# Power_Distribution_-_Pi.net
KiCad netlist of a schematic drawn in Altium Designer
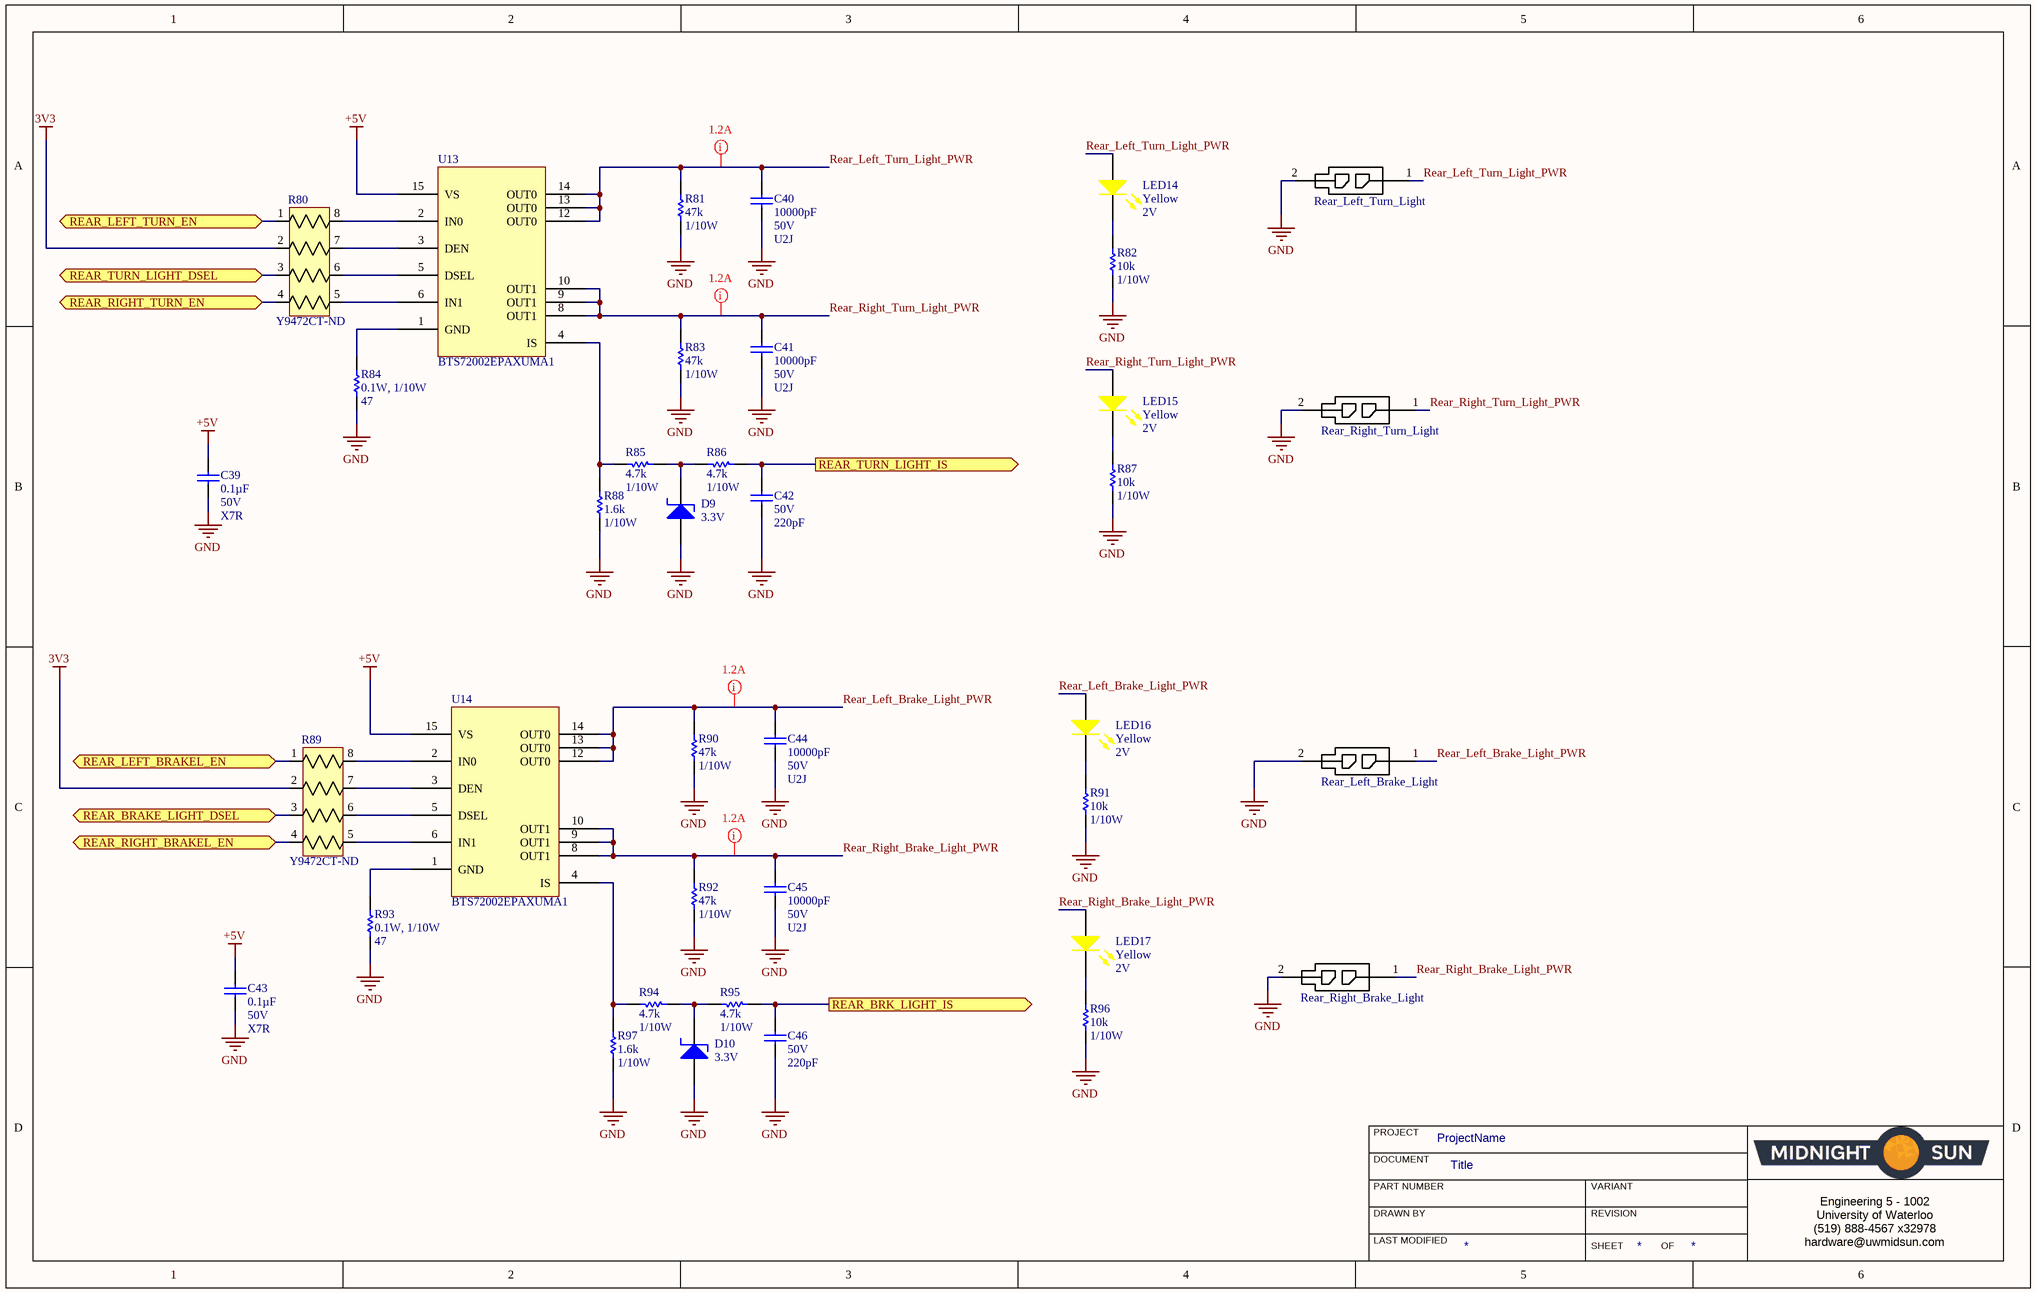
[diagram p0: Power Distribution - Pi.SchDoc]

(export (version "E")
  (design (tool "Eeschema 10.0.6"))
  (components
    (comp (ref "C39")
      (value "CAP CER 0.1UF 50V 10% X7R 0603")
      (footprint "CAP, 0603")
      (description "0.10µF ±10% 50V Ceramic Capacitor X7R 0603 (1608 Metric)")
      (fields
        (field (name "TOLERANCE") "±10%")
        (field (name "CAPACITANCE") "0.1µF")
        (field (name "VOLTAGE") "50V")
        (field (name "TEMPERATURE COEFFICIENT") "X7R")
      )
      (libsource (lib "Schematic Diagrams") (part "CAP CER 0.1UF 50V 10% X7R 0603"))
    )
    (comp (ref "C40")
      (value "CAP CER 10nF 50V 5% X7R 0603")
      (footprint "CAP, 0603")
      (description "10000pF ±5% 50V Ceramic Capacitor U2J 0603 (1608 Metric)")
      (fields
        (field (name "TOLERANCE") "±5%")
        (field (name "CAPACITANCE") "10000pF")
        (field (name "VOLTAGE") "50V")
        (field (name "TEMPERATURE COEFFICIENT") "U2J")
      )
      (libsource (lib "Schematic Diagrams") (part "CAP CER 10nF 50V 5% X7R 0603"))
    )
    (comp (ref "C41")
      (value "CAP CER 10nF 50V 5% X7R 0603")
      (footprint "CAP, 0603")
      (description "10000pF ±5% 50V Ceramic Capacitor U2J 0603 (1608 Metric)")
      (fields
        (field (name "TOLERANCE") "±5%")
        (field (name "CAPACITANCE") "10000pF")
        (field (name "VOLTAGE") "50V")
        (field (name "TEMPERATURE COEFFICIENT") "U2J")
      )
      (libsource (lib "Schematic Diagrams") (part "CAP CER 10nF 50V 5% X7R 0603"))
    )
    (comp (ref "C42")
      (value "CAP CER 220PF 50V C0G/NP0 0603")
      (footprint "CAP, 0603")
      (description "220pF ±5% 50V Ceramic Capacitor C0G, NP0 0603 (1608 Metric)")
      (fields
        (field (name "MANUFACTURER") "KEMET")
        (field (name "TOLERANCE") "5%")
        (field (name "VOLTAGE RATING") "50V")
        (field (name "CAPACITANCE") "220pF")
      )
      (libsource (lib "Schematic Diagrams") (part "CAP CER 220PF 50V C0G/NP0 0603"))
    )
    (comp (ref "C43")
      (value "CAP CER 0.1UF 50V 10% X7R 0603")
      (footprint "CAP, 0603")
      (description "0.10µF ±10% 50V Ceramic Capacitor X7R 0603 (1608 Metric)")
      (fields
        (field (name "TOLERANCE") "±10%")
        (field (name "CAPACITANCE") "0.1µF")
        (field (name "VOLTAGE") "50V")
        (field (name "TEMPERATURE COEFFICIENT") "X7R")
      )
      (libsource (lib "Schematic Diagrams") (part "CAP CER 0.1UF 50V 10% X7R 0603"))
    )
    (comp (ref "C44")
      (value "CAP CER 10nF 50V 5% X7R 0603")
      (footprint "CAP, 0603")
      (description "10000pF ±5% 50V Ceramic Capacitor U2J 0603 (1608 Metric)")
      (fields
        (field (name "TOLERANCE") "±5%")
        (field (name "CAPACITANCE") "10000pF")
        (field (name "VOLTAGE") "50V")
        (field (name "TEMPERATURE COEFFICIENT") "U2J")
      )
      (libsource (lib "Schematic Diagrams") (part "CAP CER 10nF 50V 5% X7R 0603"))
    )
    (comp (ref "C45")
      (value "CAP CER 10nF 50V 5% X7R 0603")
      (footprint "CAP, 0603")
      (description "10000pF ±5% 50V Ceramic Capacitor U2J 0603 (1608 Metric)")
      (fields
        (field (name "TOLERANCE") "±5%")
        (field (name "CAPACITANCE") "10000pF")
        (field (name "VOLTAGE") "50V")
        (field (name "TEMPERATURE COEFFICIENT") "U2J")
      )
      (libsource (lib "Schematic Diagrams") (part "CAP CER 10nF 50V 5% X7R 0603"))
    )
    (comp (ref "C46")
      (value "CAP CER 220PF 50V C0G/NP0 0603")
      (footprint "CAP, 0603")
      (description "220pF ±5% 50V Ceramic Capacitor C0G, NP0 0603 (1608 Metric)")
      (fields
        (field (name "MANUFACTURER") "KEMET")
        (field (name "TOLERANCE") "5%")
        (field (name "VOLTAGE RATING") "50V")
        (field (name "CAPACITANCE") "220pF")
      )
      (libsource (lib "Schematic Diagrams") (part "CAP CER 220PF 50V C0G/NP0 0603"))
    )
    (comp (ref "D9")
      (value "DIODE ZENER 3.3V 200MW SOD323")
      (footprint "sod-323")
      (description "Zener Diode 3.3V 200mW ±5% Surface Mount SOD-323")
      (fields (field (name "VOLTAGE") "3.3V"))
      (libsource (lib "Schematic Diagrams") (part "DIODE ZENER 3.3V 200MW SOD323"))
    )
    (comp (ref "D10")
      (value "DIODE ZENER 3.3V 200MW SOD323")
      (footprint "sod-323")
      (description "Zener Diode 3.3V 200mW ±5% Surface Mount SOD-323")
      (fields (field (name "VOLTAGE") "3.3V"))
      (libsource (lib "Schematic Diagrams") (part "DIODE ZENER 3.3V 200MW SOD323"))
    )
    (comp (ref "LED14")
      (value "LED YELLOW CLEAR 2.1V 0603")
      (footprint "LED_0603")
      (description "Yellow 590nm LED Indication - Discrete 2V 0603 (1608 Metric)")
      (fields
        (field (name "MANUFACTURER") "Wurth Electronics Inc.")
        (field (name "MANUFACTURER PART NUMBER") "150060YS75000")
        (field (name "COLOR") "Yellow")
        (field (name "VOLTAGE - FORWARD (VF) (TYP)") "2V")
      )
      (libsource (lib "Schematic Diagrams") (part "LED YELLOW CLEAR 2.1V 0603"))
    )
    (comp (ref "LED15")
      (value "LED YELLOW CLEAR 2.1V 0603")
      (footprint "LED_0603")
      (description "Yellow 590nm LED Indication - Discrete 2V 0603 (1608 Metric)")
      (fields
        (field (name "MANUFACTURER") "Wurth Electronics Inc.")
        (field (name "MANUFACTURER PART NUMBER") "150060YS75000")
        (field (name "COLOR") "Yellow")
        (field (name "VOLTAGE - FORWARD (VF) (TYP)") "2V")
      )
      (libsource (lib "Schematic Diagrams") (part "LED YELLOW CLEAR 2.1V 0603"))
    )
    (comp (ref "LED16")
      (value "LED YELLOW CLEAR 2.1V 0603")
      (footprint "LED_0603")
      (description "Yellow 590nm LED Indication - Discrete 2V 0603 (1608 Metric)")
      (fields
        (field (name "MANUFACTURER") "Wurth Electronics Inc.")
        (field (name "MANUFACTURER PART NUMBER") "150060YS75000")
        (field (name "COLOR") "Yellow")
        (field (name "VOLTAGE - FORWARD (VF) (TYP)") "2V")
      )
      (libsource (lib "Schematic Diagrams") (part "LED YELLOW CLEAR 2.1V 0603"))
    )
    (comp (ref "LED17")
      (value "LED YELLOW CLEAR 2.1V 0603")
      (footprint "LED_0603")
      (description "Yellow 590nm LED Indication - Discrete 2V 0603 (1608 Metric)")
      (fields
        (field (name "MANUFACTURER") "Wurth Electronics Inc.")
        (field (name "MANUFACTURER PART NUMBER") "150060YS75000")
        (field (name "COLOR") "Yellow")
        (field (name "VOLTAGE - FORWARD (VF) (TYP)") "2V")
      )
      (libsource (lib "Schematic Diagrams") (part "LED YELLOW CLEAR 2.1V 0603"))
    )
    (comp (ref "R80")
      (value "RES ARRAY 4 RES 4.7K OHM 1206")
      (footprint "RES ARRAY 4RES 1206")
      (fields (field (name "TOLERANCE") "±5%") (field (name "SUPPLIER PART NUMBER 1") "Y9472CT-ND"))
      (libsource (lib "Schematic Diagrams") (part "RES ARRAY 4 RES 4.7K OHM 1206"))
    )
    (comp (ref "R81")
      (value "RES 47K OHM 1% 1/10W 0603")
      (footprint "RES, 0603")
      (description "47 kOhms ±1% 0.1W, 1/10W Chip Resistor 0603 (1608 Metric) Automotive AEC-Q200 Thick Film")
      (fields
        (field (name "MANUFACTURER") "Panasonic")
        (field (name "MANUFACTURER PART NUMBER") "ERJ3EKF4702V")
        (field (name "RESISTANCE") "47k")
        (field (name "POWER RATING") "1/10W")
      )
      (libsource (lib "Schematic Diagrams") (part "RES 47K OHM 1% 1/10W 0603"))
    )
    (comp (ref "R82")
      (value "RES 10K OHM 1% 1/10W 0603")
      (footprint "RES, 0603")
      (description "RES SMD 10K OHM 1% 1/10W 0603")
      (fields
        (field (name "TOLERANCE") "±1%")
        (field (name "RESISTANCE") "10k")
        (field (name "POWER") "1/10W")
      )
      (libsource (lib "Schematic Diagrams") (part "RES 10K OHM 1% 1/10W 0603"))
    )
    (comp (ref "R83")
      (value "RES 47K OHM 1% 1/10W 0603")
      (footprint "RES, 0603")
      (description "47 kOhms ±1% 0.1W, 1/10W Chip Resistor 0603 (1608 Metric) Automotive AEC-Q200 Thick Film")
      (fields
        (field (name "MANUFACTURER") "Panasonic")
        (field (name "MANUFACTURER PART NUMBER") "ERJ3EKF4702V")
        (field (name "RESISTANCE") "47k")
        (field (name "POWER RATING") "1/10W")
      )
      (libsource (lib "Schematic Diagrams") (part "RES 47K OHM 1% 1/10W 0603"))
    )
    (comp (ref "R84")
      (value "RES SMD 47 OHM 1% 1/10W 0603")
      (footprint "RES, 0603")
      (fields
        (field (name "TOLERANCE") "±1%")
        (field (name "POWER (WATTS)") "0.1W, 1/10W")
        (field (name "VALUES") "47")
      )
      (libsource (lib "Schematic Diagrams") (part "RES SMD 47 OHM 1% 1/10W 0603"))
    )
    (comp (ref "R85")
      (value "RES 4.7K OHM 1% 1/10W 0603")
      (footprint "RES, 0603")
      (description "4.7k Ohm ±1% 0.1W, 1/10W Chip Resistor 0603 (1608 Metric) Moisture Resistant Thick Film")
      (fields
        (field (name "TOLERANCE") "±1%")
        (field (name "RESISTANCE (OHMS)") "4.7k")
        (field (name "POWER (WATTS)") "1/10W")
      )
      (libsource (lib "Schematic Diagrams") (part "RES 4.7K OHM 1% 1/10W 0603"))
    )
    (comp (ref "R86")
      (value "RES 4.7K OHM 1% 1/10W 0603")
      (footprint "RES, 0603")
      (description "4.7k Ohm ±1% 0.1W, 1/10W Chip Resistor 0603 (1608 Metric) Moisture Resistant Thick Film")
      (fields
        (field (name "TOLERANCE") "±1%")
        (field (name "RESISTANCE (OHMS)") "4.7k")
        (field (name "POWER (WATTS)") "1/10W")
      )
      (libsource (lib "Schematic Diagrams") (part "RES 4.7K OHM 1% 1/10W 0603"))
    )
    (comp (ref "R87")
      (value "RES 10K OHM 1% 1/10W 0603")
      (footprint "RES, 0603")
      (description "RES SMD 10K OHM 1% 1/10W 0603")
      (fields
        (field (name "TOLERANCE") "±1%")
        (field (name "RESISTANCE") "10k")
        (field (name "POWER") "1/10W")
      )
      (libsource (lib "Schematic Diagrams") (part "RES 10K OHM 1% 1/10W 0603"))
    )
    (comp (ref "R88")
      (value "RES 1.6K OHM 1% 1/10W 0603")
      (footprint "RES, 0603")
      (description "1.6 kOhms ±1% 0.1W, 1/10W Chip Resistor 0603 (1608 Metric) Moisture Resistant Thick Film")
      (fields
        (field (name "MANUFACTURER") "Yageo")
        (field (name "MANUFACTURER PART NUMBER") "RC0603FR-071K6L")
        (field (name "RESISTANCE") "1.6k")
        (field (name "POWER RATING") "1/10W")
      )
      (libsource (lib "Schematic Diagrams") (part "RES 1.6K OHM 1% 1/10W 0603"))
    )
    (comp (ref "R89")
      (value "RES ARRAY 4 RES 4.7K OHM 1206")
      (footprint "RES ARRAY 4RES 1206")
      (fields (field (name "TOLERANCE") "±5%") (field (name "SUPPLIER PART NUMBER 1") "Y9472CT-ND"))
      (libsource (lib "Schematic Diagrams") (part "RES ARRAY 4 RES 4.7K OHM 1206"))
    )
    (comp (ref "R90")
      (value "RES 47K OHM 1% 1/10W 0603")
      (footprint "RES, 0603")
      (description "47 kOhms ±1% 0.1W, 1/10W Chip Resistor 0603 (1608 Metric) Automotive AEC-Q200 Thick Film")
      (fields
        (field (name "MANUFACTURER") "Panasonic")
        (field (name "MANUFACTURER PART NUMBER") "ERJ3EKF4702V")
        (field (name "RESISTANCE") "47k")
        (field (name "POWER RATING") "1/10W")
      )
      (libsource (lib "Schematic Diagrams") (part "RES 47K OHM 1% 1/10W 0603"))
    )
    (comp (ref "R91")
      (value "RES 10K OHM 1% 1/10W 0603")
      (footprint "RES, 0603")
      (description "RES SMD 10K OHM 1% 1/10W 0603")
      (fields
        (field (name "TOLERANCE") "±1%")
        (field (name "RESISTANCE") "10k")
        (field (name "POWER") "1/10W")
      )
      (libsource (lib "Schematic Diagrams") (part "RES 10K OHM 1% 1/10W 0603"))
    )
    (comp (ref "R92")
      (value "RES 47K OHM 1% 1/10W 0603")
      (footprint "RES, 0603")
      (description "47 kOhms ±1% 0.1W, 1/10W Chip Resistor 0603 (1608 Metric) Automotive AEC-Q200 Thick Film")
      (fields
        (field (name "MANUFACTURER") "Panasonic")
        (field (name "MANUFACTURER PART NUMBER") "ERJ3EKF4702V")
        (field (name "RESISTANCE") "47k")
        (field (name "POWER RATING") "1/10W")
      )
      (libsource (lib "Schematic Diagrams") (part "RES 47K OHM 1% 1/10W 0603"))
    )
    (comp (ref "R93")
      (value "RES SMD 47 OHM 1% 1/10W 0603")
      (footprint "RES, 0603")
      (fields
        (field (name "TOLERANCE") "±1%")
        (field (name "POWER (WATTS)") "0.1W, 1/10W")
        (field (name "VALUES") "47")
      )
      (libsource (lib "Schematic Diagrams") (part "RES SMD 47 OHM 1% 1/10W 0603"))
    )
    (comp (ref "R94")
      (value "RES 4.7K OHM 1% 1/10W 0603")
      (footprint "RES, 0603")
      (description "4.7k Ohm ±1% 0.1W, 1/10W Chip Resistor 0603 (1608 Metric) Moisture Resistant Thick Film")
      (fields
        (field (name "TOLERANCE") "±1%")
        (field (name "RESISTANCE (OHMS)") "4.7k")
        (field (name "POWER (WATTS)") "1/10W")
      )
      (libsource (lib "Schematic Diagrams") (part "RES 4.7K OHM 1% 1/10W 0603"))
    )
    (comp (ref "R95")
      (value "RES 4.7K OHM 1% 1/10W 0603")
      (footprint "RES, 0603")
      (description "4.7k Ohm ±1% 0.1W, 1/10W Chip Resistor 0603 (1608 Metric) Moisture Resistant Thick Film")
      (fields
        (field (name "TOLERANCE") "±1%")
        (field (name "RESISTANCE (OHMS)") "4.7k")
        (field (name "POWER (WATTS)") "1/10W")
      )
      (libsource (lib "Schematic Diagrams") (part "RES 4.7K OHM 1% 1/10W 0603"))
    )
    (comp (ref "R96")
      (value "RES 10K OHM 1% 1/10W 0603")
      (footprint "RES, 0603")
      (description "RES SMD 10K OHM 1% 1/10W 0603")
      (fields
        (field (name "TOLERANCE") "±1%")
        (field (name "RESISTANCE") "10k")
        (field (name "POWER") "1/10W")
      )
      (libsource (lib "Schematic Diagrams") (part "RES 10K OHM 1% 1/10W 0603"))
    )
    (comp (ref "R97")
      (value "RES 1.6K OHM 1% 1/10W 0603")
      (footprint "RES, 0603")
      (description "1.6 kOhms ±1% 0.1W, 1/10W Chip Resistor 0603 (1608 Metric) Moisture Resistant Thick Film")
      (fields
        (field (name "MANUFACTURER") "Yageo")
        (field (name "MANUFACTURER PART NUMBER") "RC0603FR-071K6L")
        (field (name "RESISTANCE") "1.6k")
        (field (name "POWER RATING") "1/10W")
      )
      (libsource (lib "Schematic Diagrams") (part "RES 1.6K OHM 1% 1/10W 0603"))
    )
    (comp (ref "Rear_Left_Brake_Light")
      (value "CONN 2POS MICRO-FIT 3mm")
      (footprint "CONN, 2POS MICRO-FIT")
      (description "Connector Header Through Hole 2 position")
      (fields (field (name "MANUFACTURER") "Molex") (field (name "MANUFACTURER PART NUMBER") "43045-0227"))
      (libsource (lib "Schematic Diagrams") (part "CONN 2POS MICRO-FIT 3mm"))
    )
    (comp (ref "Rear_Left_Turn_Light")
      (value "CONN 2POS MICRO-FIT 3mm")
      (footprint "CONN, 2POS MICRO-FIT")
      (description "Connector Header Through Hole 2 position")
      (fields (field (name "MANUFACTURER") "Molex") (field (name "MANUFACTURER PART NUMBER") "43045-0227"))
      (libsource (lib "Schematic Diagrams") (part "CONN 2POS MICRO-FIT 3mm"))
    )
    (comp (ref "Rear_Right_Brake_Light")
      (value "CONN 2POS MICRO-FIT 3mm")
      (footprint "CONN, 2POS MICRO-FIT")
      (description "Connector Header Through Hole 2 position")
      (fields (field (name "MANUFACTURER") "Molex") (field (name "MANUFACTURER PART NUMBER") "43045-0227"))
      (libsource (lib "Schematic Diagrams") (part "CONN 2POS MICRO-FIT 3mm"))
    )
    (comp (ref "Rear_Right_Turn_Light")
      (value "CONN 2POS MICRO-FIT 3mm")
      (footprint "CONN, 2POS MICRO-FIT")
      (description "Connector Header Through Hole 2 position")
      (fields (field (name "MANUFACTURER") "Molex") (field (name "MANUFACTURER PART NUMBER") "43045-0227"))
      (libsource (lib "Schematic Diagrams") (part "CONN 2POS MICRO-FIT 3mm"))
    )
    (comp (ref "U13")
      (value "IC LOAD SWITCH BTS7200-2EPA PG-TSDSO-14_1")
      (footprint "IC LOAD SWITCH PG-TSDSO-14-22")
      (description "Power Switch/Driver 1:1 N-Channel 1.2A PG-TSDSO-14-22")
      (fields
        (field (name "MANUFACTURER") "Infineon")
        (field (name "MANUFACTURER PART NUMBER") "BTS72002EPAXUMA1")
      )
      (libsource (lib "Schematic Diagrams") (part "IC LOAD SWITCH BTS7200-2EPA PG-TSDSO-14_1"))
    )
    (comp (ref "U14")
      (value "IC LOAD SWITCH BTS7200-2EPA PG-TSDSO-14_1")
      (footprint "IC LOAD SWITCH PG-TSDSO-14-22")
      (description "Power Switch/Driver 1:1 N-Channel 1.2A PG-TSDSO-14-22")
      (fields
        (field (name "MANUFACTURER") "Infineon")
        (field (name "MANUFACTURER PART NUMBER") "BTS72002EPAXUMA1")
      )
      (libsource (lib "Schematic Diagrams") (part "IC LOAD SWITCH BTS7200-2EPA PG-TSDSO-14_1"))
    )
  )
  (nets
    (net (code "1") (name "+5V") (class "Default")
      (node (ref "C39") (pin "1") (pinfunction "1_1") (pintype "passive"))
      (node (ref "C43") (pin "1") (pinfunction "1_1") (pintype "passive"))
      (node (ref "U13") (pin "15") (pinfunction "VS_15") (pintype "passive"))
      (node (ref "U14") (pin "15") (pinfunction "VS_15") (pintype "passive"))
    )
    (net (code "2") (name "/REAR_BRAKE_LIGHT_DSEL") (class "Default")
      (node (ref "R89") (pin "3") (pinfunction "3_3") (pintype "passive"))
    )
    (net (code "3") (name "/REAR_BRK_LIGHT_IS") (class "Default")
      (node (ref "C46") (pin "1") (pinfunction "1_1") (pintype "passive"))
      (node (ref "R95") (pin "1") (pinfunction "1_1") (pintype "passive"))
    )
    (net (code "4") (name "/REAR_LEFT_BRAKEL_EN") (class "Default")
      (node (ref "R89") (pin "1") (pinfunction "1_1") (pintype "passive"))
    )
    (net (code "5") (name "/REAR_LEFT_TURN_EN") (class "Default")
      (node (ref "R80") (pin "1") (pinfunction "1_1") (pintype "passive"))
    )
    (net (code "6") (name "/REAR_RIGHT_BRAKEL_EN") (class "Default")
      (node (ref "R89") (pin "4") (pinfunction "4_4") (pintype "passive"))
    )
    (net (code "7") (name "/REAR_RIGHT_TURN_EN") (class "Default")
      (node (ref "R80") (pin "4") (pinfunction "4_4") (pintype "passive"))
    )
    (net (code "8") (name "/REAR_TURN_LIGHT_DSEL") (class "Default")
      (node (ref "R80") (pin "3") (pinfunction "3_3") (pintype "passive"))
    )
    (net (code "9") (name "/REAR_TURN_LIGHT_IS") (class "Default")
      (node (ref "C42") (pin "1") (pinfunction "1_1") (pintype "passive"))
      (node (ref "R86") (pin "1") (pinfunction "1_1") (pintype "passive"))
    )
    (net (code "10") (name "/Rear_Left_Brake_Light_PWR") (class "Default")
      (node (ref "C44") (pin "1") (pinfunction "1_1") (pintype "passive"))
      (node (ref "LED16") (pin "1") (pinfunction "A_1") (pintype "passive"))
      (node (ref "R90") (pin "1") (pinfunction "1_1") (pintype "passive"))
      (node (ref "Rear_Left_Brake_Light") (pin "1") (pinfunction "1_1") (pintype "passive"))
      (node (ref "U14") (pin "12") (pinfunction "OUT0_12") (pintype "passive"))
      (node (ref "U14") (pin "13") (pinfunction "OUT0_13") (pintype "passive"))
      (node (ref "U14") (pin "14") (pinfunction "OUT0_14") (pintype "passive"))
    )
    (net (code "11") (name "/Rear_Left_Turn_Light_PWR") (class "Default")
      (node (ref "C40") (pin "1") (pinfunction "1_1") (pintype "passive"))
      (node (ref "LED14") (pin "1") (pinfunction "A_1") (pintype "passive"))
      (node (ref "R81") (pin "1") (pinfunction "1_1") (pintype "passive"))
      (node (ref "Rear_Left_Turn_Light") (pin "1") (pinfunction "1_1") (pintype "passive"))
      (node (ref "U13") (pin "12") (pinfunction "OUT0_12") (pintype "passive"))
      (node (ref "U13") (pin "13") (pinfunction "OUT0_13") (pintype "passive"))
      (node (ref "U13") (pin "14") (pinfunction "OUT0_14") (pintype "passive"))
    )
    (net (code "12") (name "/Rear_Right_Brake_Light_PWR") (class "Default")
      (node (ref "C45") (pin "1") (pinfunction "1_1") (pintype "passive"))
      (node (ref "LED17") (pin "1") (pinfunction "A_1") (pintype "passive"))
      (node (ref "R92") (pin "1") (pinfunction "1_1") (pintype "passive"))
      (node (ref "Rear_Right_Brake_Light") (pin "1") (pinfunction "1_1") (pintype "passive"))
      (node (ref "U14") (pin "10") (pinfunction "OUT1_10") (pintype "passive"))
      (node (ref "U14") (pin "8") (pinfunction "OUT1_8") (pintype "passive"))
      (node (ref "U14") (pin "9") (pinfunction "OUT1_9") (pintype "passive"))
    )
    (net (code "13") (name "/Rear_Right_Turn_Light_PWR") (class "Default")
      (node (ref "C41") (pin "1") (pinfunction "1_1") (pintype "passive"))
      (node (ref "LED15") (pin "1") (pinfunction "A_1") (pintype "passive"))
      (node (ref "R83") (pin "1") (pinfunction "1_1") (pintype "passive"))
      (node (ref "Rear_Right_Turn_Light") (pin "1") (pinfunction "1_1") (pintype "passive"))
      (node (ref "U13") (pin "10") (pinfunction "OUT1_10") (pintype "passive"))
      (node (ref "U13") (pin "8") (pinfunction "OUT1_8") (pintype "passive"))
      (node (ref "U13") (pin "9") (pinfunction "OUT1_9") (pintype "passive"))
    )
    (net (code "14") (name "3V3") (class "Default")
      (node (ref "R80") (pin "2") (pinfunction "2_2") (pintype "passive"))
      (node (ref "R89") (pin "2") (pinfunction "2_2") (pintype "passive"))
    )
    (net (code "15") (name "GND") (class "Default")
      (node (ref "C39") (pin "2") (pinfunction "2_2") (pintype "passive"))
      (node (ref "C40") (pin "2") (pinfunction "2_2") (pintype "passive"))
      (node (ref "C41") (pin "2") (pinfunction "2_2") (pintype "passive"))
      (node (ref "C42") (pin "2") (pinfunction "2_2") (pintype "passive"))
      (node (ref "C43") (pin "2") (pinfunction "2_2") (pintype "passive"))
      (node (ref "C44") (pin "2") (pinfunction "2_2") (pintype "passive"))
      (node (ref "C45") (pin "2") (pinfunction "2_2") (pintype "passive"))
      (node (ref "C46") (pin "2") (pinfunction "2_2") (pintype "passive"))
      (node (ref "D10") (pin "1") (pinfunction "A_1") (pintype "passive"))
      (node (ref "D9") (pin "1") (pinfunction "A_1") (pintype "passive"))
      (node (ref "R81") (pin "2") (pinfunction "2_2") (pintype "passive"))
      (node (ref "R82") (pin "2") (pinfunction "2_2") (pintype "passive"))
      (node (ref "R83") (pin "2") (pinfunction "2_2") (pintype "passive"))
      (node (ref "R84") (pin "2") (pinfunction "2_2") (pintype "passive"))
      (node (ref "R87") (pin "2") (pinfunction "2_2") (pintype "passive"))
      (node (ref "R88") (pin "2") (pinfunction "2_2") (pintype "passive"))
      (node (ref "R90") (pin "2") (pinfunction "2_2") (pintype "passive"))
      (node (ref "R91") (pin "2") (pinfunction "2_2") (pintype "passive"))
      (node (ref "R92") (pin "2") (pinfunction "2_2") (pintype "passive"))
      (node (ref "R93") (pin "2") (pinfunction "2_2") (pintype "passive"))
      (node (ref "R96") (pin "2") (pinfunction "2_2") (pintype "passive"))
      (node (ref "R97") (pin "2") (pinfunction "2_2") (pintype "passive"))
      (node (ref "Rear_Left_Brake_Light") (pin "2") (pinfunction "2_2") (pintype "passive"))
      (node (ref "Rear_Left_Turn_Light") (pin "2") (pinfunction "2_2") (pintype "passive"))
      (node (ref "Rear_Right_Brake_Light") (pin "2") (pinfunction "2_2") (pintype "passive"))
      (node (ref "Rear_Right_Turn_Light") (pin "2") (pinfunction "2_2") (pintype "passive"))
    )
    (net (code "16") (name "Net-(D9-K)") (class "Default")
      (node (ref "D9") (pin "2") (pinfunction "K_2") (pintype "passive"))
      (node (ref "R85") (pin "1") (pinfunction "1_1") (pintype "passive"))
      (node (ref "R86") (pin "2") (pinfunction "2_2") (pintype "passive"))
    )
    (net (code "17") (name "Net-(D10-K)") (class "Default")
      (node (ref "D10") (pin "2") (pinfunction "K_2") (pintype "passive"))
      (node (ref "R94") (pin "1") (pinfunction "1_1") (pintype "passive"))
      (node (ref "R95") (pin "2") (pinfunction "2_2") (pintype "passive"))
    )
    (net (code "18") (name "Net-(LED14-K)") (class "Default")
      (node (ref "LED14") (pin "2") (pinfunction "K_2") (pintype "passive"))
      (node (ref "R82") (pin "1") (pinfunction "1_1") (pintype "passive"))
    )
    (net (code "19") (name "Net-(LED15-K)") (class "Default")
      (node (ref "LED15") (pin "2") (pinfunction "K_2") (pintype "passive"))
      (node (ref "R87") (pin "1") (pinfunction "1_1") (pintype "passive"))
    )
    (net (code "20") (name "Net-(LED16-K)") (class "Default")
      (node (ref "LED16") (pin "2") (pinfunction "K_2") (pintype "passive"))
      (node (ref "R91") (pin "1") (pinfunction "1_1") (pintype "passive"))
    )
    (net (code "21") (name "Net-(LED17-K)") (class "Default")
      (node (ref "LED17") (pin "2") (pinfunction "K_2") (pintype "passive"))
      (node (ref "R96") (pin "1") (pinfunction "1_1") (pintype "passive"))
    )
    (net (code "22") (name "Net-(U13-DEN)") (class "Default")
      (node (ref "R80") (pin "7") (pinfunction "7_7") (pintype "passive"))
      (node (ref "U13") (pin "3") (pinfunction "DEN_3") (pintype "passive"))
    )
    (net (code "23") (name "Net-(U13-DSEL)") (class "Default")
      (node (ref "R80") (pin "6") (pinfunction "6_6") (pintype "passive"))
      (node (ref "U13") (pin "5") (pinfunction "DSEL_5") (pintype "passive"))
    )
    (net (code "24") (name "Net-(U13-GND)") (class "Default")
      (node (ref "R84") (pin "1") (pinfunction "1_1") (pintype "passive"))
      (node (ref "U13") (pin "1") (pinfunction "GND_1") (pintype "passive"))
    )
    (net (code "25") (name "Net-(U13-IN0)") (class "Default")
      (node (ref "R80") (pin "8") (pinfunction "8_8") (pintype "passive"))
      (node (ref "U13") (pin "2") (pinfunction "IN0_2") (pintype "passive"))
    )
    (net (code "26") (name "Net-(U13-IN1)") (class "Default")
      (node (ref "R80") (pin "5") (pinfunction "5_5") (pintype "passive"))
      (node (ref "U13") (pin "6") (pinfunction "IN1_6") (pintype "passive"))
    )
    (net (code "27") (name "Net-(U13-IS)") (class "Default")
      (node (ref "R85") (pin "2") (pinfunction "2_2") (pintype "passive"))
      (node (ref "R88") (pin "1") (pinfunction "1_1") (pintype "passive"))
      (node (ref "U13") (pin "4") (pinfunction "IS_4") (pintype "passive"))
    )
    (net (code "28") (name "Net-(U14-DEN)") (class "Default")
      (node (ref "R89") (pin "7") (pinfunction "7_7") (pintype "passive"))
      (node (ref "U14") (pin "3") (pinfunction "DEN_3") (pintype "passive"))
    )
    (net (code "29") (name "Net-(U14-DSEL)") (class "Default")
      (node (ref "R89") (pin "6") (pinfunction "6_6") (pintype "passive"))
      (node (ref "U14") (pin "5") (pinfunction "DSEL_5") (pintype "passive"))
    )
    (net (code "30") (name "Net-(U14-GND)") (class "Default")
      (node (ref "R93") (pin "1") (pinfunction "1_1") (pintype "passive"))
      (node (ref "U14") (pin "1") (pinfunction "GND_1") (pintype "passive"))
    )
    (net (code "31") (name "Net-(U14-IN0)") (class "Default")
      (node (ref "R89") (pin "8") (pinfunction "8_8") (pintype "passive"))
      (node (ref "U14") (pin "2") (pinfunction "IN0_2") (pintype "passive"))
    )
    (net (code "32") (name "Net-(U14-IN1)") (class "Default")
      (node (ref "R89") (pin "5") (pinfunction "5_5") (pintype "passive"))
      (node (ref "U14") (pin "6") (pinfunction "IN1_6") (pintype "passive"))
    )
    (net (code "33") (name "Net-(U14-IS)") (class "Default")
      (node (ref "R94") (pin "2") (pinfunction "2_2") (pintype "passive"))
      (node (ref "R97") (pin "1") (pinfunction "1_1") (pintype "passive"))
      (node (ref "U14") (pin "4") (pinfunction "IS_4") (pintype "passive"))
    )
  )
)
